# wisp-6-main.net
KiCad netlist of a schematic drawn in Altium Designer
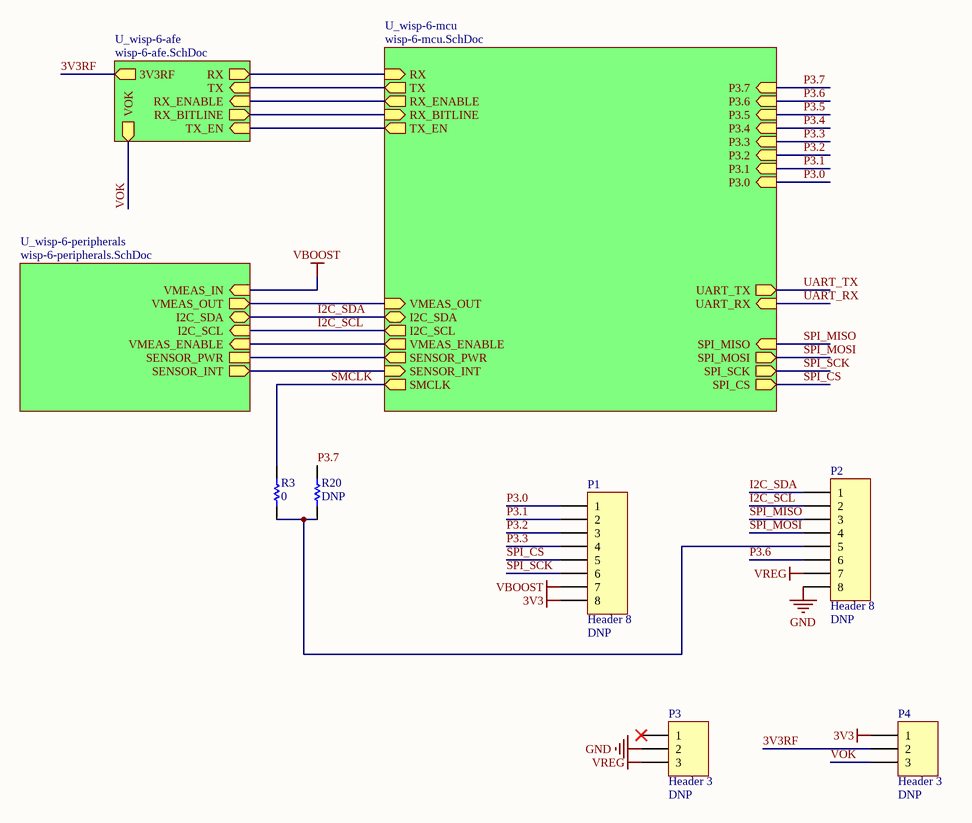
[diagram p0: wisp-6-main.SchDoc]

(export (version "E")
  (design (tool "Eeschema 10.0.6"))
  (components
    (comp (ref "P1")
      (value "Header 8")
      (footprint "HDR1X8")
      (description "Header, 8-Pin")
      (fields (field (name "ALTIUM_VALUE") "DNP") (field (name "PUBLISHER") "Altium Limited"))
      (libsource (lib "Miscellaneous Connectors") (part "Header 8"))
    )
    (comp (ref "P2")
      (value "Header 8")
      (footprint "HDR1X8")
      (description "Header, 8-Pin")
      (fields (field (name "ALTIUM_VALUE") "DNP") (field (name "PUBLISHER") "Altium Limited"))
      (libsource (lib "Miscellaneous Connectors") (part "Header 8"))
    )
    (comp (ref "P3")
      (value "Header 3")
      (footprint "HDR1X3")
      (description "Header, 3-Pin")
      (fields (field (name "ALTIUM_VALUE") "DNP") (field (name "PUBLISHER") "Altium Limited"))
      (libsource (lib "Miscellaneous Connectors") (part "Header 3"))
    )
    (comp (ref "P4")
      (value "Header 3")
      (footprint "HDR1X3")
      (description "Header, 3-Pin")
      (fields (field (name "ALTIUM_VALUE") "DNP") (field (name "PUBLISHER") "Altium Limited"))
      (libsource (lib "Miscellaneous Connectors") (part "Header 3"))
    )
    (comp (ref "R3")
      (value "0")
      (footprint "0402")
      (description "RES 0 OHM JUMPER 1/16W 0402")
      (fields
        (field (name "MANUFACTURER") "YAGEO")
        (field (name "MANUFACTURER PART NUMBER") "RC0402JR-070RL")
      )
      (libsource (lib "WISP6") (part "R-0-0.063W-*-0402"))
    )
    (comp (ref "R20")
      (value "DNP")
      (footprint "0402")
      (description "Chip Resistor (Surface Mount)")
      (fields (field (name "Comment") "Generic resistor"))
      (libsource (lib "WISP6") (part "res"))
    )
  )
  (nets
    (net (code "1") (name "/3V3RF") (class "Default")
      (node (ref "P4") (pin "2") (pinfunction "2_2") (pintype "passive"))
    )
    (net (code "2") (name "/I2C_SCL") (class "Default")
      (node (ref "P2") (pin "2") (pinfunction "2_2") (pintype "passive"))
    )
    (net (code "3") (name "/I2C_SDA") (class "Default")
      (node (ref "P2") (pin "1") (pinfunction "1_1") (pintype "passive"))
    )
    (net (code "4") (name "/P3.0") (class "Default")
      (node (ref "P1") (pin "1") (pinfunction "1_1") (pintype "passive"))
    )
    (net (code "5") (name "/P3.1") (class "Default")
      (node (ref "P1") (pin "2") (pinfunction "2_2") (pintype "passive"))
    )
    (net (code "6") (name "/P3.2") (class "Default")
      (node (ref "P1") (pin "3") (pinfunction "3_3") (pintype "passive"))
    )
    (net (code "7") (name "/P3.3") (class "Default")
      (node (ref "P1") (pin "4") (pinfunction "4_4") (pintype "passive"))
    )
    (net (code "10") (name "/P3.6") (class "Default")
      (node (ref "P2") (pin "6") (pinfunction "6_6") (pintype "passive"))
    )
    (net (code "11") (name "/P3.7") (class "Default")
      (node (ref "R20") (pin "2") (pinfunction "2_2") (pintype "passive"))
    )
    (net (code "17") (name "/SMCLK") (class "Default")
      (node (ref "R3") (pin "2") (pinfunction "2_2") (pintype "passive"))
    )
    (net (code "18") (name "/SPI_CS") (class "Default")
      (node (ref "P1") (pin "5") (pinfunction "5_5") (pintype "passive"))
    )
    (net (code "19") (name "/SPI_MISO") (class "Default")
      (node (ref "P2") (pin "3") (pinfunction "3_3") (pintype "passive"))
    )
    (net (code "20") (name "/SPI_MOSI") (class "Default")
      (node (ref "P2") (pin "4") (pinfunction "4_4") (pintype "passive"))
    )
    (net (code "21") (name "/SPI_SCK") (class "Default")
      (node (ref "P1") (pin "6") (pinfunction "6_6") (pintype "passive"))
    )
    (net (code "28") (name "/VOK") (class "Default")
      (node (ref "P4") (pin "3") (pinfunction "3_3") (pintype "passive"))
    )
    (net (code "29") (name "3V3") (class "Default")
      (node (ref "P1") (pin "8") (pinfunction "8_8") (pintype "passive"))
      (node (ref "P4") (pin "1") (pinfunction "1_1") (pintype "passive"))
    )
    (net (code "30") (name "GND") (class "Default")
      (node (ref "P2") (pin "8") (pinfunction "8_8") (pintype "passive"))
      (node (ref "P3") (pin "2") (pinfunction "2_2") (pintype "passive"))
    )
    (net (code "31") (name "Net-(P2-Pad5)") (class "Default")
      (node (ref "P2") (pin "5") (pinfunction "5_5") (pintype "passive"))
      (node (ref "R20") (pin "1") (pinfunction "1_1") (pintype "passive"))
      (node (ref "R3") (pin "1") (pinfunction "1_1") (pintype "passive"))
    )
    (net (code "32") (name "VBOOST") (class "Default")
      (node (ref "P1") (pin "7") (pinfunction "7_7") (pintype "passive"))
    )
    (net (code "33") (name "VREG") (class "Default")
      (node (ref "P2") (pin "7") (pinfunction "7_7") (pintype "passive"))
      (node (ref "P3") (pin "3") (pinfunction "3_3") (pintype "passive"))
    )
    (net (code "34") (name "unconnected-(P3-Pad1)") (class "Default")
      (node (ref "P3") (pin "1") (pinfunction "1_1") (pintype "passive+no_connect"))
    )
  )
)
